# 9_LPDDR4_SDRAM1.net
KiCad netlist of a schematic drawn in Altium Designer
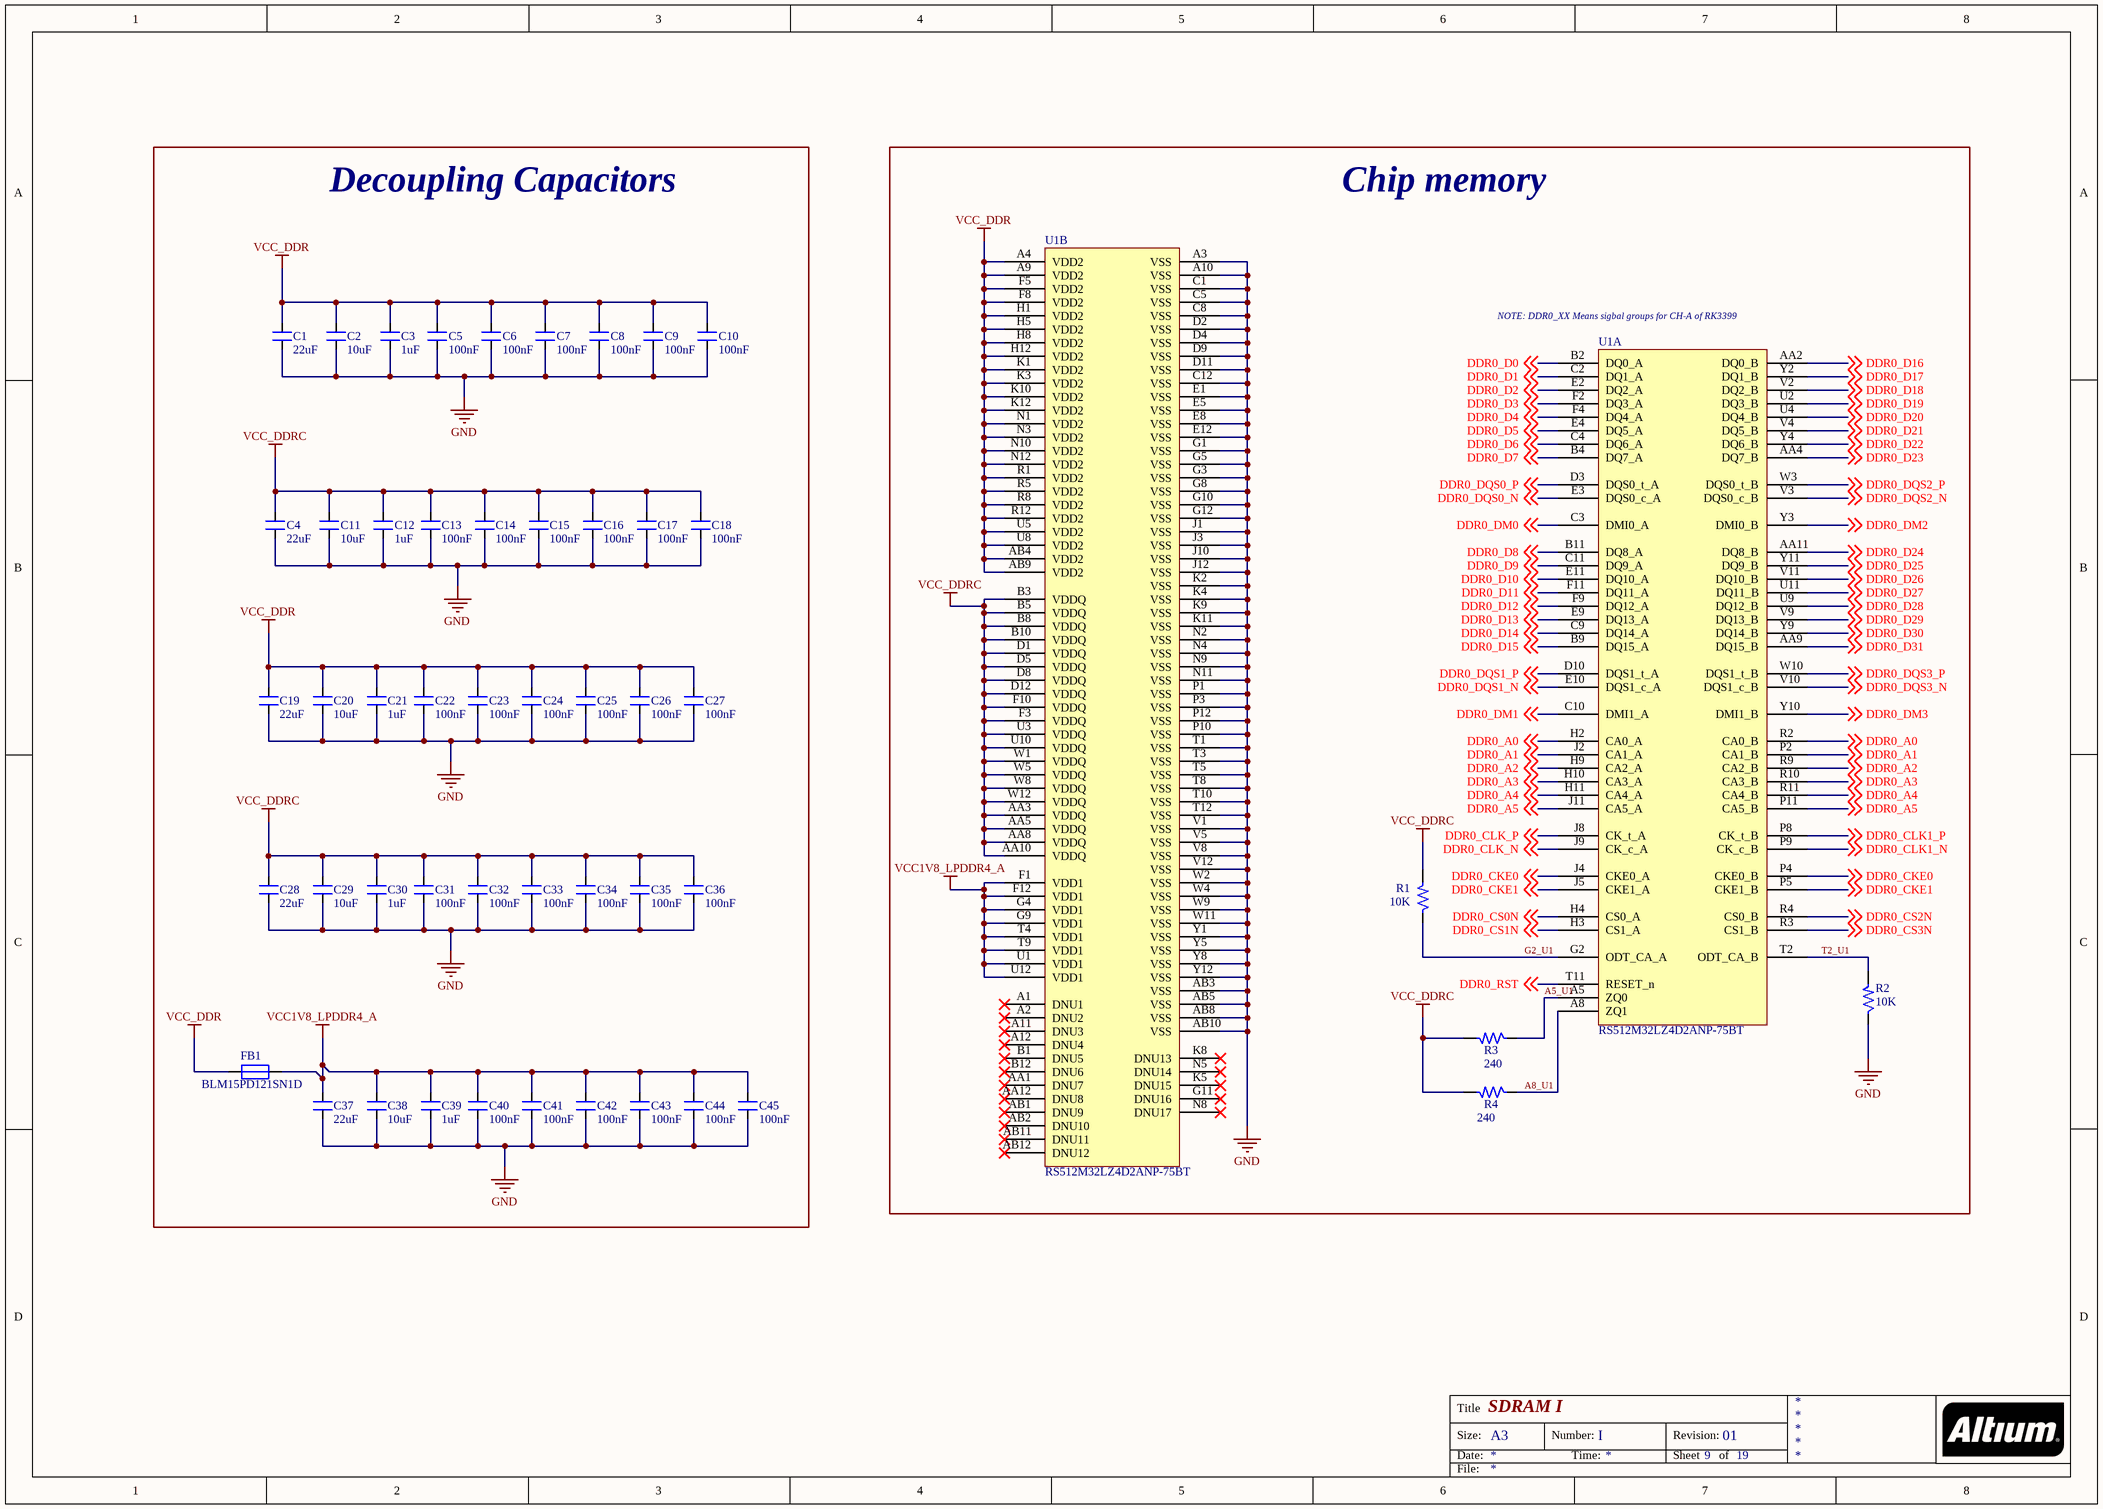
[diagram p0: [9] LPDDR4_SDRAM1.SchDoc]

(export (version "E")
  (design (tool "Eeschema 10.0.6"))
  (components
    (comp (ref "C1")
      (value "22uF")
      (footprint "CAP_0402")
      (description "22µF ±20% 6.3V Ceramic Capacitor X5R 0402 (1005 Metric)")
      (fields
        (field (name "MANUFACTURER") "Murata Electronics")
        (field (name "MANUFACTURER PART NUMBER") "CL05A226MQ5N6J8")
      )
      (libsource (lib "EsteemPCB_SOM_Course_intlib") (part "CAP_22uF-6.3V-20%-0402"))
    )
    (comp (ref "C2")
      (value "10uF")
      (footprint "CAP_0402")
      (description "10µF ±20% 10V Ceramic Capacitor X5R 0402 (1005 Metric)")
      (fields
        (field (name "MANUFACTURER PART NUMBER") "CL05A106MP5NUNC")
        (field (name "MANUFACTURER") "Samsung Electro-Mechanics")
      )
      (libsource (lib "EsteemPCB_SOM_Course_intlib") (part "CAP_10uF-10V-20%-0402"))
    )
    (comp (ref "C3")
      (value "1uF")
      (footprint "CAP_0201")
      (description "1µF ±20% 16V Ceramic Capacitor X5R 0201 (0603 Metric)")
      (fields
        (field (name "MANUFACTURER") "Samsung Electro-Mechanics")
        (field (name "MANUFACTURER PART NUMBER") "CL03A105MO3NRNH")
      )
      (libsource (lib "EsteemPCB_SOM_Course_intlib") (part "CAP_1uF-16V-10%-0201"))
    )
    (comp (ref "C4")
      (value "22uF")
      (footprint "CAP_0402")
      (description "22µF ±20% 6.3V Ceramic Capacitor X5R 0402 (1005 Metric)")
      (fields
        (field (name "MANUFACTURER") "Murata Electronics")
        (field (name "MANUFACTURER PART NUMBER") "CL05A226MQ5N6J8")
      )
      (libsource (lib "EsteemPCB_SOM_Course_intlib") (part "CAP_22uF-6.3V-20%-0402"))
    )
    (comp (ref "C5")
      (value "100nF")
      (footprint "CAP_0201")
      (description "0.1µF ±10% 25V Ceramic Capacitor X5R 0201 (0603 Metric)")
      (fields
        (field (name "MANUFACTURER") "TDK Corporation")
        (field (name "MANUFACTURER PART NUMBER") "C0603X5R1E104K030BB")
      )
      (libsource (lib "EsteemPCB_SOM_Course_intlib") (part "CAP_100nF-25V-10%-0201"))
    )
    (comp (ref "C6")
      (value "100nF")
      (footprint "CAP_0201")
      (description "0.1µF ±10% 25V Ceramic Capacitor X5R 0201 (0603 Metric)")
      (fields
        (field (name "MANUFACTURER") "TDK Corporation")
        (field (name "MANUFACTURER PART NUMBER") "C0603X5R1E104K030BB")
      )
      (libsource (lib "EsteemPCB_SOM_Course_intlib") (part "CAP_100nF-25V-10%-0201"))
    )
    (comp (ref "C7")
      (value "100nF")
      (footprint "CAP_0201")
      (description "0.1µF ±10% 25V Ceramic Capacitor X5R 0201 (0603 Metric)")
      (fields
        (field (name "MANUFACTURER") "TDK Corporation")
        (field (name "MANUFACTURER PART NUMBER") "C0603X5R1E104K030BB")
      )
      (libsource (lib "EsteemPCB_SOM_Course_intlib") (part "CAP_100nF-25V-10%-0201"))
    )
    (comp (ref "C8")
      (value "100nF")
      (footprint "CAP_0201")
      (description "0.1µF ±10% 25V Ceramic Capacitor X5R 0201 (0603 Metric)")
      (fields
        (field (name "MANUFACTURER") "TDK Corporation")
        (field (name "MANUFACTURER PART NUMBER") "C0603X5R1E104K030BB")
      )
      (libsource (lib "EsteemPCB_SOM_Course_intlib") (part "CAP_100nF-25V-10%-0201"))
    )
    (comp (ref "C9")
      (value "100nF")
      (footprint "CAP_0201")
      (description "0.1µF ±10% 25V Ceramic Capacitor X5R 0201 (0603 Metric)")
      (fields
        (field (name "MANUFACTURER") "TDK Corporation")
        (field (name "MANUFACTURER PART NUMBER") "C0603X5R1E104K030BB")
      )
      (libsource (lib "EsteemPCB_SOM_Course_intlib") (part "CAP_100nF-25V-10%-0201"))
    )
    (comp (ref "C10")
      (value "100nF")
      (footprint "CAP_0201")
      (description "0.1µF ±10% 25V Ceramic Capacitor X5R 0201 (0603 Metric)")
      (fields
        (field (name "MANUFACTURER") "TDK Corporation")
        (field (name "MANUFACTURER PART NUMBER") "C0603X5R1E104K030BB")
      )
      (libsource (lib "EsteemPCB_SOM_Course_intlib") (part "CAP_100nF-25V-10%-0201"))
    )
    (comp (ref "C11")
      (value "10uF")
      (footprint "CAP_0402")
      (description "10µF ±20% 10V Ceramic Capacitor X5R 0402 (1005 Metric)")
      (fields
        (field (name "MANUFACTURER PART NUMBER") "CL05A106MP5NUNC")
        (field (name "MANUFACTURER") "Samsung Electro-Mechanics")
      )
      (libsource (lib "EsteemPCB_SOM_Course_intlib") (part "CAP_10uF-10V-20%-0402"))
    )
    (comp (ref "C12")
      (value "1uF")
      (footprint "CAP_0201")
      (description "1µF ±20% 16V Ceramic Capacitor X5R 0201 (0603 Metric)")
      (fields
        (field (name "MANUFACTURER") "Samsung Electro-Mechanics")
        (field (name "MANUFACTURER PART NUMBER") "CL03A105MO3NRNH")
      )
      (libsource (lib "EsteemPCB_SOM_Course_intlib") (part "CAP_1uF-16V-10%-0201"))
    )
    (comp (ref "C13")
      (value "100nF")
      (footprint "CAP_0201")
      (description "0.1µF ±10% 25V Ceramic Capacitor X5R 0201 (0603 Metric)")
      (fields
        (field (name "MANUFACTURER") "TDK Corporation")
        (field (name "MANUFACTURER PART NUMBER") "C0603X5R1E104K030BB")
      )
      (libsource (lib "EsteemPCB_SOM_Course_intlib") (part "CAP_100nF-25V-10%-0201"))
    )
    (comp (ref "C14")
      (value "100nF")
      (footprint "CAP_0201")
      (description "0.1µF ±10% 25V Ceramic Capacitor X5R 0201 (0603 Metric)")
      (fields
        (field (name "MANUFACTURER") "TDK Corporation")
        (field (name "MANUFACTURER PART NUMBER") "C0603X5R1E104K030BB")
      )
      (libsource (lib "EsteemPCB_SOM_Course_intlib") (part "CAP_100nF-25V-10%-0201"))
    )
    (comp (ref "C15")
      (value "100nF")
      (footprint "CAP_0201")
      (description "0.1µF ±10% 25V Ceramic Capacitor X5R 0201 (0603 Metric)")
      (fields
        (field (name "MANUFACTURER") "TDK Corporation")
        (field (name "MANUFACTURER PART NUMBER") "C0603X5R1E104K030BB")
      )
      (libsource (lib "EsteemPCB_SOM_Course_intlib") (part "CAP_100nF-25V-10%-0201"))
    )
    (comp (ref "C16")
      (value "100nF")
      (footprint "CAP_0201")
      (description "0.1µF ±10% 25V Ceramic Capacitor X5R 0201 (0603 Metric)")
      (fields
        (field (name "MANUFACTURER") "TDK Corporation")
        (field (name "MANUFACTURER PART NUMBER") "C0603X5R1E104K030BB")
      )
      (libsource (lib "EsteemPCB_SOM_Course_intlib") (part "CAP_100nF-25V-10%-0201"))
    )
    (comp (ref "C17")
      (value "100nF")
      (footprint "CAP_0201")
      (description "0.1µF ±10% 25V Ceramic Capacitor X5R 0201 (0603 Metric)")
      (fields
        (field (name "MANUFACTURER") "TDK Corporation")
        (field (name "MANUFACTURER PART NUMBER") "C0603X5R1E104K030BB")
      )
      (libsource (lib "EsteemPCB_SOM_Course_intlib") (part "CAP_100nF-25V-10%-0201"))
    )
    (comp (ref "C18")
      (value "100nF")
      (footprint "CAP_0201")
      (description "0.1µF ±10% 25V Ceramic Capacitor X5R 0201 (0603 Metric)")
      (fields
        (field (name "MANUFACTURER") "TDK Corporation")
        (field (name "MANUFACTURER PART NUMBER") "C0603X5R1E104K030BB")
      )
      (libsource (lib "EsteemPCB_SOM_Course_intlib") (part "CAP_100nF-25V-10%-0201"))
    )
    (comp (ref "C19")
      (value "22uF")
      (footprint "CAP_0402")
      (description "22µF ±20% 6.3V Ceramic Capacitor X5R 0402 (1005 Metric)")
      (fields
        (field (name "MANUFACTURER") "Murata Electronics")
        (field (name "MANUFACTURER PART NUMBER") "CL05A226MQ5N6J8")
      )
      (libsource (lib "EsteemPCB_SOM_Course_intlib") (part "CAP_22uF-6.3V-20%-0402"))
    )
    (comp (ref "C20")
      (value "10uF")
      (footprint "CAP_0402")
      (description "10µF ±20% 10V Ceramic Capacitor X5R 0402 (1005 Metric)")
      (fields
        (field (name "MANUFACTURER PART NUMBER") "CL05A106MP5NUNC")
        (field (name "MANUFACTURER") "Samsung Electro-Mechanics")
      )
      (libsource (lib "EsteemPCB_SOM_Course_intlib") (part "CAP_10uF-10V-20%-0402"))
    )
    (comp (ref "C21")
      (value "1uF")
      (footprint "CAP_0201")
      (description "1µF ±20% 16V Ceramic Capacitor X5R 0201 (0603 Metric)")
      (fields
        (field (name "MANUFACTURER") "Samsung Electro-Mechanics")
        (field (name "MANUFACTURER PART NUMBER") "CL03A105MO3NRNH")
      )
      (libsource (lib "EsteemPCB_SOM_Course_intlib") (part "CAP_1uF-16V-10%-0201"))
    )
    (comp (ref "C22")
      (value "100nF")
      (footprint "CAP_0201")
      (description "0.1µF ±10% 25V Ceramic Capacitor X5R 0201 (0603 Metric)")
      (fields
        (field (name "MANUFACTURER") "TDK Corporation")
        (field (name "MANUFACTURER PART NUMBER") "C0603X5R1E104K030BB")
      )
      (libsource (lib "EsteemPCB_SOM_Course_intlib") (part "CAP_100nF-25V-10%-0201"))
    )
    (comp (ref "C23")
      (value "100nF")
      (footprint "CAP_0201")
      (description "0.1µF ±10% 25V Ceramic Capacitor X5R 0201 (0603 Metric)")
      (fields
        (field (name "MANUFACTURER") "TDK Corporation")
        (field (name "MANUFACTURER PART NUMBER") "C0603X5R1E104K030BB")
      )
      (libsource (lib "EsteemPCB_SOM_Course_intlib") (part "CAP_100nF-25V-10%-0201"))
    )
    (comp (ref "C24")
      (value "100nF")
      (footprint "CAP_0201")
      (description "0.1µF ±10% 25V Ceramic Capacitor X5R 0201 (0603 Metric)")
      (fields
        (field (name "MANUFACTURER") "TDK Corporation")
        (field (name "MANUFACTURER PART NUMBER") "C0603X5R1E104K030BB")
      )
      (libsource (lib "EsteemPCB_SOM_Course_intlib") (part "CAP_100nF-25V-10%-0201"))
    )
    (comp (ref "C25")
      (value "100nF")
      (footprint "CAP_0201")
      (description "0.1µF ±10% 25V Ceramic Capacitor X5R 0201 (0603 Metric)")
      (fields
        (field (name "MANUFACTURER") "TDK Corporation")
        (field (name "MANUFACTURER PART NUMBER") "C0603X5R1E104K030BB")
      )
      (libsource (lib "EsteemPCB_SOM_Course_intlib") (part "CAP_100nF-25V-10%-0201"))
    )
    (comp (ref "C26")
      (value "100nF")
      (footprint "CAP_0201")
      (description "0.1µF ±10% 25V Ceramic Capacitor X5R 0201 (0603 Metric)")
      (fields
        (field (name "MANUFACTURER") "TDK Corporation")
        (field (name "MANUFACTURER PART NUMBER") "C0603X5R1E104K030BB")
      )
      (libsource (lib "EsteemPCB_SOM_Course_intlib") (part "CAP_100nF-25V-10%-0201"))
    )
    (comp (ref "C27")
      (value "100nF")
      (footprint "CAP_0201")
      (description "0.1µF ±10% 25V Ceramic Capacitor X5R 0201 (0603 Metric)")
      (fields
        (field (name "MANUFACTURER") "TDK Corporation")
        (field (name "MANUFACTURER PART NUMBER") "C0603X5R1E104K030BB")
      )
      (libsource (lib "EsteemPCB_SOM_Course_intlib") (part "CAP_100nF-25V-10%-0201"))
    )
    (comp (ref "C28")
      (value "22uF")
      (footprint "CAP_0402")
      (description "22µF ±20% 6.3V Ceramic Capacitor X5R 0402 (1005 Metric)")
      (fields
        (field (name "MANUFACTURER") "Murata Electronics")
        (field (name "MANUFACTURER PART NUMBER") "CL05A226MQ5N6J8")
      )
      (libsource (lib "EsteemPCB_SOM_Course_intlib") (part "CAP_22uF-6.3V-20%-0402"))
    )
    (comp (ref "C29")
      (value "10uF")
      (footprint "CAP_0402")
      (description "10µF ±20% 10V Ceramic Capacitor X5R 0402 (1005 Metric)")
      (fields
        (field (name "MANUFACTURER PART NUMBER") "CL05A106MP5NUNC")
        (field (name "MANUFACTURER") "Samsung Electro-Mechanics")
      )
      (libsource (lib "EsteemPCB_SOM_Course_intlib") (part "CAP_10uF-10V-20%-0402"))
    )
    (comp (ref "C30")
      (value "1uF")
      (footprint "CAP_0201")
      (description "1µF ±20% 16V Ceramic Capacitor X5R 0201 (0603 Metric)")
      (fields
        (field (name "MANUFACTURER") "Samsung Electro-Mechanics")
        (field (name "MANUFACTURER PART NUMBER") "CL03A105MO3NRNH")
      )
      (libsource (lib "EsteemPCB_SOM_Course_intlib") (part "CAP_1uF-16V-10%-0201"))
    )
    (comp (ref "C31")
      (value "100nF")
      (footprint "CAP_0201")
      (description "0.1µF ±10% 25V Ceramic Capacitor X5R 0201 (0603 Metric)")
      (fields
        (field (name "MANUFACTURER") "TDK Corporation")
        (field (name "MANUFACTURER PART NUMBER") "C0603X5R1E104K030BB")
      )
      (libsource (lib "EsteemPCB_SOM_Course_intlib") (part "CAP_100nF-25V-10%-0201"))
    )
    (comp (ref "C32")
      (value "100nF")
      (footprint "CAP_0201")
      (description "0.1µF ±10% 25V Ceramic Capacitor X5R 0201 (0603 Metric)")
      (fields
        (field (name "MANUFACTURER") "TDK Corporation")
        (field (name "MANUFACTURER PART NUMBER") "C0603X5R1E104K030BB")
      )
      (libsource (lib "EsteemPCB_SOM_Course_intlib") (part "CAP_100nF-25V-10%-0201"))
    )
    (comp (ref "C33")
      (value "100nF")
      (footprint "CAP_0201")
      (description "0.1µF ±10% 25V Ceramic Capacitor X5R 0201 (0603 Metric)")
      (fields
        (field (name "MANUFACTURER") "TDK Corporation")
        (field (name "MANUFACTURER PART NUMBER") "C0603X5R1E104K030BB")
      )
      (libsource (lib "EsteemPCB_SOM_Course_intlib") (part "CAP_100nF-25V-10%-0201"))
    )
    (comp (ref "C34")
      (value "100nF")
      (footprint "CAP_0201")
      (description "0.1µF ±10% 25V Ceramic Capacitor X5R 0201 (0603 Metric)")
      (fields
        (field (name "MANUFACTURER") "TDK Corporation")
        (field (name "MANUFACTURER PART NUMBER") "C0603X5R1E104K030BB")
      )
      (libsource (lib "EsteemPCB_SOM_Course_intlib") (part "CAP_100nF-25V-10%-0201"))
    )
    (comp (ref "C35")
      (value "100nF")
      (footprint "CAP_0201")
      (description "0.1µF ±10% 25V Ceramic Capacitor X5R 0201 (0603 Metric)")
      (fields
        (field (name "MANUFACTURER") "TDK Corporation")
        (field (name "MANUFACTURER PART NUMBER") "C0603X5R1E104K030BB")
      )
      (libsource (lib "EsteemPCB_SOM_Course_intlib") (part "CAP_100nF-25V-10%-0201"))
    )
    (comp (ref "C36")
      (value "100nF")
      (footprint "CAP_0201")
      (description "0.1µF ±10% 25V Ceramic Capacitor X5R 0201 (0603 Metric)")
      (fields
        (field (name "MANUFACTURER") "TDK Corporation")
        (field (name "MANUFACTURER PART NUMBER") "C0603X5R1E104K030BB")
      )
      (libsource (lib "EsteemPCB_SOM_Course_intlib") (part "CAP_100nF-25V-10%-0201"))
    )
    (comp (ref "C37")
      (value "22uF")
      (footprint "CAP_0402")
      (description "22µF ±20% 6.3V Ceramic Capacitor X5R 0402 (1005 Metric)")
      (fields
        (field (name "MANUFACTURER") "Murata Electronics")
        (field (name "MANUFACTURER PART NUMBER") "CL05A226MQ5N6J8")
      )
      (libsource (lib "EsteemPCB_SOM_Course_intlib") (part "CAP_22uF-6.3V-20%-0402"))
    )
    (comp (ref "C38")
      (value "10uF")
      (footprint "CAP_0402")
      (description "10µF ±20% 10V Ceramic Capacitor X5R 0402 (1005 Metric)")
      (fields
        (field (name "MANUFACTURER PART NUMBER") "CL05A106MP5NUNC")
        (field (name "MANUFACTURER") "Samsung Electro-Mechanics")
      )
      (libsource (lib "EsteemPCB_SOM_Course_intlib") (part "CAP_10uF-10V-20%-0402"))
    )
    (comp (ref "C39")
      (value "1uF")
      (footprint "CAP_0201")
      (description "1µF ±20% 16V Ceramic Capacitor X5R 0201 (0603 Metric)")
      (fields
        (field (name "MANUFACTURER") "Samsung Electro-Mechanics")
        (field (name "MANUFACTURER PART NUMBER") "CL03A105MO3NRNH")
      )
      (libsource (lib "EsteemPCB_SOM_Course_intlib") (part "CAP_1uF-16V-10%-0201"))
    )
    (comp (ref "C40")
      (value "100nF")
      (footprint "CAP_0201")
      (description "0.1µF ±10% 25V Ceramic Capacitor X5R 0201 (0603 Metric)")
      (fields
        (field (name "MANUFACTURER") "TDK Corporation")
        (field (name "MANUFACTURER PART NUMBER") "C0603X5R1E104K030BB")
      )
      (libsource (lib "EsteemPCB_SOM_Course_intlib") (part "CAP_100nF-25V-10%-0201"))
    )
    (comp (ref "C41")
      (value "100nF")
      (footprint "CAP_0201")
      (description "0.1µF ±10% 25V Ceramic Capacitor X5R 0201 (0603 Metric)")
      (fields
        (field (name "MANUFACTURER") "TDK Corporation")
        (field (name "MANUFACTURER PART NUMBER") "C0603X5R1E104K030BB")
      )
      (libsource (lib "EsteemPCB_SOM_Course_intlib") (part "CAP_100nF-25V-10%-0201"))
    )
    (comp (ref "C42")
      (value "100nF")
      (footprint "CAP_0201")
      (description "0.1µF ±10% 25V Ceramic Capacitor X5R 0201 (0603 Metric)")
      (fields
        (field (name "MANUFACTURER") "TDK Corporation")
        (field (name "MANUFACTURER PART NUMBER") "C0603X5R1E104K030BB")
      )
      (libsource (lib "EsteemPCB_SOM_Course_intlib") (part "CAP_100nF-25V-10%-0201"))
    )
    (comp (ref "C43")
      (value "100nF")
      (footprint "CAP_0201")
      (description "0.1µF ±10% 25V Ceramic Capacitor X5R 0201 (0603 Metric)")
      (fields
        (field (name "MANUFACTURER") "TDK Corporation")
        (field (name "MANUFACTURER PART NUMBER") "C0603X5R1E104K030BB")
      )
      (libsource (lib "EsteemPCB_SOM_Course_intlib") (part "CAP_100nF-25V-10%-0201"))
    )
    (comp (ref "C44")
      (value "100nF")
      (footprint "CAP_0201")
      (description "0.1µF ±10% 25V Ceramic Capacitor X5R 0201 (0603 Metric)")
      (fields
        (field (name "MANUFACTURER") "TDK Corporation")
        (field (name "MANUFACTURER PART NUMBER") "C0603X5R1E104K030BB")
      )
      (libsource (lib "EsteemPCB_SOM_Course_intlib") (part "CAP_100nF-25V-10%-0201"))
    )
    (comp (ref "C45")
      (value "100nF")
      (footprint "CAP_0201")
      (description "0.1µF ±10% 25V Ceramic Capacitor X5R 0201 (0603 Metric)")
      (fields
        (field (name "MANUFACTURER") "TDK Corporation")
        (field (name "MANUFACTURER PART NUMBER") "C0603X5R1E104K030BB")
      )
      (libsource (lib "EsteemPCB_SOM_Course_intlib") (part "CAP_100nF-25V-10%-0201"))
    )
    (comp (ref "FB1")
      (value "BLM15PD121SN1D")
      (footprint "RES_0402")
      (description "120 Ohms @ 100MHz 1 Power Line Ferrite Bead 0402 (1005 Metric) 1.3A 90mOhm")
      (fields (field (name "MANUFACTURER") "Murata Electronics"))
      (libsource (lib "EsteemPCB_SOM_Course_intlib") (part "FB_120R-1.3A-100Mhz-0402"))
    )
    (comp (ref "R1")
      (value "10K")
      (footprint "RES_0201")
      (description "10 kOhms ±1% 0.05W, 1/20W Chip Resistor 0201 (0603 Metric) Thick Film")
      (fields
        (field (name "MANUFACTURER") "Stackpole Electronics Inc")
        (field (name "MANUFACTURER PART NUMBER") "RMCF0201FT10K0")
      )
      (libsource (lib "EsteemPCB_SOM_Course_intlib") (part "RES_10K-0.05W-1%-0201"))
    )
    (comp (ref "R2")
      (value "10K")
      (footprint "RES_0201")
      (description "10 kOhms ±1% 0.05W, 1/20W Chip Resistor 0201 (0603 Metric) Thick Film")
      (fields
        (field (name "MANUFACTURER") "Stackpole Electronics Inc")
        (field (name "MANUFACTURER PART NUMBER") "RMCF0201FT10K0")
      )
      (libsource (lib "EsteemPCB_SOM_Course_intlib") (part "RES_10K-0.05W-1%-0201"))
    )
    (comp (ref "R3")
      (value "240")
      (footprint "RES_0201")
      (description "10 kOhms ±1% 0.05W, 1/20W Chip Resistor 0201 (0603 Metric) Thick Film")
      (fields
        (field (name "MANUFACTURER") "Stackpole Electronics Inc")
        (field (name "MANUFACTURER PART NUMBER") "RMCF0201FT10K0")
      )
      (libsource (lib "EsteemPCB_SOM_Course_intlib") (part "RES_10K-0.05W-1%-0201"))
    )
    (comp (ref "R4")
      (value "240")
      (footprint "RES_0201")
      (description "10 kOhms ±1% 0.05W, 1/20W Chip Resistor 0201 (0603 Metric) Thick Film")
      (fields
        (field (name "MANUFACTURER") "Stackpole Electronics Inc")
        (field (name "MANUFACTURER PART NUMBER") "RMCF0201FT10K0")
      )
      (libsource (lib "EsteemPCB_SOM_Course_intlib") (part "RES_10K-0.05W-1%-0201"))
    )
    (comp (ref "U1")
      (value "RS512M32LZ4D2ANP-75BT")
      (footprint "FBGA200_SMD")
      (fields (field (name "MANUFACTURER") "RAYSON"))
      (libsource (lib "EsteemPCB_SOM_Course_intlib") (part "IC_RS512M32LZ4D2ANP-75BT"))
    )
  )
  (nets
    (net (code "1") (name "/A5_U1") (class "Default")
      (node (ref "R3") (pin "1") (pinfunction "1_1") (pintype "passive"))
      (node (ref "U1") (pin "A5") (pinfunction "ZQ0_A5") (pintype "passive"))
    )
    (net (code "2") (name "/A8_U1") (class "Default")
      (node (ref "R4") (pin "1") (pinfunction "1_1") (pintype "passive"))
      (node (ref "U1") (pin "A8") (pinfunction "ZQ1_A8") (pintype "passive"))
    )
    (net (code "3") (name "/G2_U1") (class "Default")
      (node (ref "R1") (pin "1") (pinfunction "1_1") (pintype "passive"))
      (node (ref "U1") (pin "G2") (pinfunction "ODT_CA_A_G2") (pintype "passive"))
    )
    (net (code "4") (name "/T2_U1") (class "Default")
      (node (ref "R2") (pin "2") (pinfunction "2_2") (pintype "passive"))
      (node (ref "U1") (pin "T2") (pinfunction "ODT_CA_B_T2") (pintype "passive"))
    )
    (net (code "5") (name "DDR0_A0") (class "Default")
      (node (ref "U1") (pin "H2") (pinfunction "CA0_A_H2") (pintype "passive"))
      (node (ref "U1") (pin "R2") (pinfunction "CA0_B_R2") (pintype "passive"))
    )
    (net (code "6") (name "DDR0_A1") (class "Default")
      (node (ref "U1") (pin "J2") (pinfunction "CA1_A_J2") (pintype "passive"))
      (node (ref "U1") (pin "P2") (pinfunction "CA1_B_P2") (pintype "passive"))
    )
    (net (code "7") (name "DDR0_A2") (class "Default")
      (node (ref "U1") (pin "H9") (pinfunction "CA2_A_H9") (pintype "passive"))
      (node (ref "U1") (pin "R9") (pinfunction "CA2_B_R9") (pintype "passive"))
    )
    (net (code "8") (name "DDR0_A3") (class "Default")
      (node (ref "U1") (pin "H10") (pinfunction "CA3_A_H10") (pintype "passive"))
      (node (ref "U1") (pin "R10") (pinfunction "CA3_B_R10") (pintype "passive"))
    )
    (net (code "9") (name "DDR0_A4") (class "Default")
      (node (ref "U1") (pin "H11") (pinfunction "CA4_A_H11") (pintype "passive"))
      (node (ref "U1") (pin "R11") (pinfunction "CA4_B_R11") (pintype "passive"))
    )
    (net (code "10") (name "DDR0_A5") (class "Default")
      (node (ref "U1") (pin "J11") (pinfunction "CA5_A_J11") (pintype "passive"))
      (node (ref "U1") (pin "P11") (pinfunction "CA5_B_P11") (pintype "passive"))
    )
    (net (code "11") (name "DDR0_CKE0") (class "Default")
      (node (ref "U1") (pin "J4") (pinfunction "CKE0_A_J4") (pintype "passive"))
      (node (ref "U1") (pin "P4") (pinfunction "CKE0_B_P4") (pintype "passive"))
    )
    (net (code "12") (name "DDR0_CKE1") (class "Default")
      (node (ref "U1") (pin "J5") (pinfunction "CKE1_A_J5") (pintype "passive"))
      (node (ref "U1") (pin "P5") (pinfunction "CKE1_B_P5") (pintype "passive"))
    )
    (net (code "13") (name "DDR0_CLK1_N") (class "Default")
      (node (ref "U1") (pin "P9") (pinfunction "CK_c_B_P9") (pintype "passive"))
    )
    (net (code "14") (name "DDR0_CLK1_P") (class "Default")
      (node (ref "U1") (pin "P8") (pinfunction "CK_t_B_P8") (pintype "passive"))
    )
    (net (code "15") (name "DDR0_CLK_N") (class "Default")
      (node (ref "U1") (pin "J9") (pinfunction "CK_c_A_J9") (pintype "passive"))
    )
    (net (code "16") (name "DDR0_CLK_P") (class "Default")
      (node (ref "U1") (pin "J8") (pinfunction "CK_t_A_J8") (pintype "passive"))
    )
    (net (code "17") (name "DDR0_CS0N") (class "Default")
      (node (ref "U1") (pin "H4") (pinfunction "CS0_A_H4") (pintype "passive"))
    )
    (net (code "18") (name "DDR0_CS1N") (class "Default")
      (node (ref "U1") (pin "H3") (pinfunction "CS1_A_H3") (pintype "passive"))
    )
    (net (code "19") (name "DDR0_CS2N") (class "Default")
      (node (ref "U1") (pin "R4") (pinfunction "CS0_B_R4") (pintype "passive"))
    )
    (net (code "20") (name "DDR0_CS3N") (class "Default")
      (node (ref "U1") (pin "R3") (pinfunction "CS1_B_R3") (pintype "passive"))
    )
    (net (code "21") (name "DDR0_D0") (class "Default")
      (node (ref "U1") (pin "B2") (pinfunction "DQ0_A_B2") (pintype "passive"))
    )
    (net (code "22") (name "DDR0_D1") (class "Default")
      (node (ref "U1") (pin "C2") (pinfunction "DQ1_A_C2") (pintype "passive"))
    )
    (net (code "23") (name "DDR0_D2") (class "Default")
      (node (ref "U1") (pin "E2") (pinfunction "DQ2_A_E2") (pintype "passive"))
    )
    (net (code "24") (name "DDR0_D3") (class "Default")
      (node (ref "U1") (pin "F2") (pinfunction "DQ3_A_F2") (pintype "passive"))
    )
    (net (code "25") (name "DDR0_D4") (class "Default")
      (node (ref "U1") (pin "F4") (pinfunction "DQ4_A_F4") (pintype "passive"))
    )
    (net (code "26") (name "DDR0_D5") (class "Default")
      (node (ref "U1") (pin "E4") (pinfunction "DQ5_A_E4") (pintype "passive"))
    )
    (net (code "27") (name "DDR0_D6") (class "Default")
      (node (ref "U1") (pin "C4") (pinfunction "DQ6_A_C4") (pintype "passive"))
    )
    (net (code "28") (name "DDR0_D7") (class "Default")
      (node (ref "U1") (pin "B4") (pinfunction "DQ7_A_B4") (pintype "passive"))
    )
    (net (code "29") (name "DDR0_D8") (class "Default")
      (node (ref "U1") (pin "B11") (pinfunction "DQ8_A_B11") (pintype "passive"))
    )
    (net (code "30") (name "DDR0_D9") (class "Default")
      (node (ref "U1") (pin "C11") (pinfunction "DQ9_A_C11") (pintype "passive"))
    )
    (net (code "31") (name "DDR0_D10") (class "Default")
      (node (ref "U1") (pin "E11") (pinfunction "DQ10_A_E11") (pintype "passive"))
    )
    (net (code "32") (name "DDR0_D11") (class "Default")
      (node (ref "U1") (pin "F11") (pinfunction "DQ11_A_F11") (pintype "passive"))
    )
    (net (code "33") (name "DDR0_D12") (class "Default")
      (node (ref "U1") (pin "F9") (pinfunction "DQ12_A_F9") (pintype "passive"))
    )
    (net (code "34") (name "DDR0_D13") (class "Default")
      (node (ref "U1") (pin "E9") (pinfunction "DQ13_A_E9") (pintype "passive"))
    )
    (net (code "35") (name "DDR0_D14") (class "Default")
      (node (ref "U1") (pin "C9") (pinfunction "DQ14_A_C9") (pintype "passive"))
    )
    (net (code "36") (name "DDR0_D15") (class "Default")
      (node (ref "U1") (pin "B9") (pinfunction "DQ15_A_B9") (pintype "passive"))
    )
    (net (code "37") (name "DDR0_D16") (class "Default")
      (node (ref "U1") (pin "AA2") (pinfunction "DQ0_B_AA2") (pintype "passive"))
    )
    (net (code "38") (name "DDR0_D17") (class "Default")
      (node (ref "U1") (pin "Y2") (pinfunction "DQ1_B_Y2") (pintype "passive"))
    )
    (net (code "39") (name "DDR0_D18") (class "Default")
      (node (ref "U1") (pin "V2") (pinfunction "DQ2_B_V2") (pintype "passive"))
    )
    (net (code "40") (name "DDR0_D19") (class "Default")
      (node (ref "U1") (pin "U2") (pinfunction "DQ3_B_U2") (pintype "passive"))
    )
    (net (code "41") (name "DDR0_D20") (class "Default")
      (node (ref "U1") (pin "U4") (pinfunction "DQ4_B_U4") (pintype "passive"))
    )
    (net (code "42") (name "DDR0_D21") (class "Default")
      (node (ref "U1") (pin "V4") (pinfunction "DQ5_B_V4") (pintype "passive"))
    )
    (net (code "43") (name "DDR0_D22") (class "Default")
      (node (ref "U1") (pin "Y4") (pinfunction "DQ6_B_Y4") (pintype "passive"))
    )
    (net (code "44") (name "DDR0_D23") (class "Default")
      (node (ref "U1") (pin "AA4") (pinfunction "DQ7_B_AA4") (pintype "passive"))
    )
    (net (code "45") (name "DDR0_D24") (class "Default")
      (node (ref "U1") (pin "AA11") (pinfunction "DQ8_B_AA11") (pintype "passive"))
    )
    (net (code "46") (name "DDR0_D25") (class "Default")
      (node (ref "U1") (pin "Y11") (pinfunction "DQ9_B_Y11") (pintype "passive"))
    )
    (net (code "47") (name "DDR0_D26") (class "Default")
      (node (ref "U1") (pin "V11") (pinfunction "DQ10_B_V11") (pintype "passive"))
    )
    (net (code "48") (name "DDR0_D27") (class "Default")
      (node (ref "U1") (pin "U11") (pinfunction "DQ11_B_U11") (pintype "passive"))
    )
    (net (code "49") (name "DDR0_D28") (class "Default")
      (node (ref "U1") (pin "U9") (pinfunction "DQ12_B_U9") (pintype "passive"))
    )
    (net (code "50") (name "DDR0_D29") (class "Default")
      (node (ref "U1") (pin "V9") (pinfunction "DQ13_B_V9") (pintype "passive"))
    )
    (net (code "51") (name "DDR0_D30") (class "Default")
      (node (ref "U1") (pin "Y9") (pinfunction "DQ14_B_Y9") (pintype "passive"))
    )
    (net (code "52") (name "DDR0_D31") (class "Default")
      (node (ref "U1") (pin "AA9") (pinfunction "DQ15_B_AA9") (pintype "passive"))
    )
    (net (code "53") (name "DDR0_DM0") (class "Default")
      (node (ref "U1") (pin "C3") (pinfunction "DMI0_A_C3") (pintype "passive"))
    )
    (net (code "54") (name "DDR0_DM1") (class "Default")
      (node (ref "U1") (pin "C10") (pinfunction "DMI1_A_C10") (pintype "passive"))
    )
    (net (code "55") (name "DDR0_DM2") (class "Default")
      (node (ref "U1") (pin "Y3") (pinfunction "DMI0_B_Y3") (pintype "passive"))
    )
    (net (code "56") (name "DDR0_DM3") (class "Default")
      (node (ref "U1") (pin "Y10") (pinfunction "DMI1_B_Y10") (pintype "passive"))
    )
    (net (code "57") (name "DDR0_DQS0_N") (class "Default")
      (node (ref "U1") (pin "E3") (pinfunction "DQS0_c_A_E3") (pintype "passive"))
    )
    (net (code "58") (name "DDR0_DQS0_P") (class "Default")
      (node (ref "U1") (pin "D3") (pinfunction "DQS0_t_A_D3") (pintype "passive"))
    )
    (net (code "59") (name "DDR0_DQS1_N") (class "Default")
      (node (ref "U1") (pin "E10") (pinfunction "DQS1_c_A_E10") (pintype "passive"))
    )
    (net (code "60") (name "DDR0_DQS1_P") (class "Default")
      (node (ref "U1") (pin "D10") (pinfunction "DQS1_t_A_D10") (pintype "passive"))
    )
    (net (code "61") (name "DDR0_DQS2_N") (class "Default")
      (node (ref "U1") (pin "V3") (pinfunction "DQS0_c_B_V3") (pintype "passive"))
    )
    (net (code "62") (name "DDR0_DQS2_P") (class "Default")
      (node (ref "U1") (pin "W3") (pinfunction "DQS0_t_B_W3") (pintype "passive"))
    )
    (net (code "63") (name "DDR0_DQS3_N") (class "Default")
      (node (ref "U1") (pin "V10") (pinfunction "DQS1_c_B_V10") (pintype "passive"))
    )
    (net (code "64") (name "DDR0_DQS3_P") (class "Default")
      (node (ref "U1") (pin "W10") (pinfunction "DQS1_t_B_W10") (pintype "passive"))
    )
    (net (code "65") (name "DDR0_RST") (class "Default")
      (node (ref "U1") (pin "T11") (pinfunction "RESET_n_T11") (pintype "passive"))
    )
    (net (code "66") (name "GND") (class "Default")
      (node (ref "C1") (pin "1") (pinfunction "1_1") (pintype "passive"))
      (node (ref "C10") (pin "1") (pinfunction "1_1") (pintype "passive"))
      (node (ref "C11") (pin "1") (pinfunction "1_1") (pintype "passive"))
      (node (ref "C12") (pin "1") (pinfunction "1_1") (pintype "passive"))
      (node (ref "C13") (pin "1") (pinfunction "1_1") (pintype "passive"))
      (node (ref "C14") (pin "1") (pinfunction "1_1") (pintype "passive"))
      (node (ref "C15") (pin "1") (pinfunction "1_1") (pintype "passive"))
      (node (ref "C16") (pin "1") (pinfunction "1_1") (pintype "passive"))
      (node (ref "C17") (pin "1") (pinfunction "1_1") (pintype "passive"))
      (node (ref "C18") (pin "1") (pinfunction "1_1") (pintype "passive"))
      (node (ref "C19") (pin "1") (pinfunction "1_1") (pintype "passive"))
      (node (ref "C2") (pin "1") (pinfunction "1_1") (pintype "passive"))
      (node (ref "C20") (pin "1") (pinfunction "1_1") (pintype "passive"))
      (node (ref "C21") (pin "1") (pinfunction "1_1") (pintype "passive"))
      (node (ref "C22") (pin "1") (pinfunction "1_1") (pintype "passive"))
      (node (ref "C23") (pin "1") (pinfunction "1_1") (pintype "passive"))
      (node (ref "C24") (pin "1") (pinfunction "1_1") (pintype "passive"))
      (node (ref "C25") (pin "1") (pinfunction "1_1") (pintype "passive"))
      (node (ref "C26") (pin "1") (pinfunction "1_1") (pintype "passive"))
      (node (ref "C27") (pin "1") (pinfunction "1_1") (pintype "passive"))
      (node (ref "C28") (pin "1") (pinfunction "1_1") (pintype "passive"))
      (node (ref "C29") (pin "1") (pinfunction "1_1") (pintype "passive"))
      (node (ref "C3") (pin "1") (pinfunction "1_1") (pintype "passive"))
      (node (ref "C30") (pin "1") (pinfunction "1_1") (pintype "passive"))
      (node (ref "C31") (pin "1") (pinfunction "1_1") (pintype "passive"))
      (node (ref "C32") (pin "1") (pinfunction "1_1") (pintype "passive"))
      (node (ref "C33") (pin "1") (pinfunction "1_1") (pintype "passive"))
      (node (ref "C34") (pin "1") (pinfunction "1_1") (pintype "passive"))
      (node (ref "C35") (pin "1") (pinfunction "1_1") (pintype "passive"))
      (node (ref "C36") (pin "1") (pinfunction "1_1") (pintype "passive"))
      (node (ref "C37") (pin "1") (pinfunction "1_1") (pintype "passive"))
      (node (ref "C38") (pin "1") (pinfunction "1_1") (pintype "passive"))
      (node (ref "C39") (pin "1") (pinfunction "1_1") (pintype "passive"))
      (node (ref "C4") (pin "1") (pinfunction "1_1") (pintype "passive"))
      (node (ref "C40") (pin "1") (pinfunction "1_1") (pintype "passive"))
      (node (ref "C41") (pin "1") (pinfunction "1_1") (pintype "passive"))
      (node (ref "C42") (pin "1") (pinfunction "1_1") (pintype "passive"))
      (node (ref "C43") (pin "1") (pinfunction "1_1") (pintype "passive"))
      (node (ref "C44") (pin "1") (pinfunction "1_1") (pintype "passive"))
      (node (ref "C45") (pin "1") (pinfunction "1_1") (pintype "passive"))
      (node (ref "C5") (pin "1") (pinfunction "1_1") (pintype "passive"))
      (node (ref "C6") (pin "1") (pinfunction "1_1") (pintype "passive"))
      (node (ref "C7") (pin "1") (pinfunction "1_1") (pintype "passive"))
      (node (ref "C8") (pin "1") (pinfunction "1_1") (pintype "passive"))
      (node (ref "C9") (pin "1") (pinfunction "1_1") (pintype "passive"))
      (node (ref "R2") (pin "1") (pinfunction "1_1") (pintype "passive"))
      (node (ref "U1") (pin "A10") (pinfunction "VSS_A10") (pintype "passive"))
      (node (ref "U1") (pin "A3") (pinfunction "VSS_A3") (pintype "passive"))
      (node (ref "U1") (pin "AB10") (pinfunction "VSS_AB10") (pintype "passive"))
      (node (ref "U1") (pin "AB3") (pinfunction "VSS_AB3") (pintype "passive"))
      (node (ref "U1") (pin "AB5") (pinfunction "VSS_AB5") (pintype "passive"))
      (node (ref "U1") (pin "AB8") (pinfunction "VSS_AB8") (pintype "passive"))
      (node (ref "U1") (pin "C1") (pinfunction "VSS_C1") (pintype "passive"))
      (node (ref "U1") (pin "C12") (pinfunction "VSS_C12") (pintype "passive"))
      (node (ref "U1") (pin "C5") (pinfunction "VSS_C5") (pintype "passive"))
      (node (ref "U1") (pin "C8") (pinfunction "VSS_C8") (pintype "passive"))
      (node (ref "U1") (pin "D11") (pinfunction "VSS_D11") (pintype "passive"))
      (node (ref "U1") (pin "D2") (pinfunction "VSS_D2") (pintype "passive"))
      (node (ref "U1") (pin "D4") (pinfunction "VSS_D4") (pintype "passive"))
      (node (ref "U1") (pin "D9") (pinfunction "VSS_D9") (pintype "passive"))
      (node (ref "U1") (pin "E1") (pinfunction "VSS_E1") (pintype "passive"))
      (node (ref "U1") (pin "E12") (pinfunction "VSS_E12") (pintype "passive"))
      (node (ref "U1") (pin "E5") (pinfunction "VSS_E5") (pintype "passive"))
      (node (ref "U1") (pin "E8") (pinfunction "VSS_E8") (pintype "passive"))
      (node (ref "U1") (pin "G1") (pinfunction "VSS_G1") (pintype "passive"))
      (node (ref "U1") (pin "G10") (pinfunction "VSS_G10") (pintype "passive"))
      (node (ref "U1") (pin "G12") (pinfunction "VSS_G12") (pintype "passive"))
      (node (ref "U1") (pin "G3") (pinfunction "VSS_G3") (pintype "passive"))
      (node (ref "U1") (pin "G5") (pinfunction "VSS_G5") (pintype "passive"))
      (node (ref "U1") (pin "G8") (pinfunction "VSS_G8") (pintype "passive"))
      (node (ref "U1") (pin "J1") (pinfunction "VSS_J1") (pintype "passive"))
      (node (ref "U1") (pin "J10") (pinfunction "VSS_J10") (pintype "passive"))
      (node (ref "U1") (pin "J12") (pinfunction "VSS_J12") (pintype "passive"))
      (node (ref "U1") (pin "J3") (pinfunction "VSS_J3") (pintype "passive"))
      (node (ref "U1") (pin "K11") (pinfunction "VSS_K11") (pintype "passive"))
      (node (ref "U1") (pin "K2") (pinfunction "VSS_K2") (pintype "passive"))
      (node (ref "U1") (pin "K4") (pinfunction "VSS_K4") (pintype "passive"))
      (node (ref "U1") (pin "K9") (pinfunction "VSS_K9") (pintype "passive"))
      (node (ref "U1") (pin "N11") (pinfunction "VSS_N11") (pintype "passive"))
      (node (ref "U1") (pin "N2") (pinfunction "VSS_N2") (pintype "passive"))
      (node (ref "U1") (pin "N4") (pinfunction "VSS_N4") (pintype "passive"))
      (node (ref "U1") (pin "N9") (pinfunction "VSS_N9") (pintype "passive"))
      (node (ref "U1") (pin "P1") (pinfunction "VSS_P1") (pintype "passive"))
      (node (ref "U1") (pin "P10") (pinfunction "VSS_P10") (pintype "passive"))
      (node (ref "U1") (pin "P12") (pinfunction "VSS_P12") (pintype "passive"))
      (node (ref "U1") (pin "P3") (pinfunction "VSS_P3") (pintype "passive"))
      (node (ref "U1") (pin "T1") (pinfunction "VSS_T1") (pintype "passive"))
      (node (ref "U1") (pin "T10") (pinfunction "VSS_T10") (pintype "passive"))
      (node (ref "U1") (pin "T12") (pinfunction "VSS_T12") (pintype "passive"))
      (node (ref "U1") (pin "T3") (pinfunction "VSS_T3") (pintype "passive"))
      (node (ref "U1") (pin "T5") (pinfunction "VSS_T5") (pintype "passive"))
      (node (ref "U1") (pin "T8") (pinfunction "VSS_T8") (pintype "passive"))
      (node (ref "U1") (pin "V1") (pinfunction "VSS_V1") (pintype "passive"))
      (node (ref "U1") (pin "V12") (pinfunction "VSS_V12") (pintype "passive"))
      (node (ref "U1") (pin "V5") (pinfunction "VSS_V5") (pintype "passive"))
      (node (ref "U1") (pin "V8") (pinfunction "VSS_V8") (pintype "passive"))
      (node (ref "U1") (pin "W11") (pinfunction "VSS_W11") (pintype "passive"))
      (node (ref "U1") (pin "W2") (pinfunction "VSS_W2") (pintype "passive"))
      (node (ref "U1") (pin "W4") (pinfunction "VSS_W4") (pintype "passive"))
      (node (ref "U1") (pin "W9") (pinfunction "VSS_W9") (pintype "passive"))
      (node (ref "U1") (pin "Y1") (pinfunction "VSS_Y1") (pintype "passive"))
      (node (ref "U1") (pin "Y12") (pinfunction "VSS_Y12") (pintype "passive"))
      (node (ref "U1") (pin "Y5") (pinfunction "VSS_Y5") (pintype "passive"))
      (node (ref "U1") (pin "Y8") (pinfunction "VSS_Y8") (pintype "passive"))
    )
    (net (code "67") (name "VCC1V8_LPDDR4_A") (class "Default")
      (node (ref "C37") (pin "2") (pinfunction "2_2") (pintype "passive"))
      (node (ref "C38") (pin "2") (pinfunction "2_2") (pintype "passive"))
      (node (ref "C39") (pin "2") (pinfunction "2_2") (pintype "passive"))
      (node (ref "C40") (pin "2") (pinfunction "2_2") (pintype "passive"))
      (node (ref "C41") (pin "2") (pinfunction "2_2") (pintype "passive"))
      (node (ref "C42") (pin "2") (pinfunction "2_2") (pintype "passive"))
      (node (ref "C43") (pin "2") (pinfunction "2_2") (pintype "passive"))
      (node (ref "C44") (pin "2") (pinfunction "2_2") (pintype "passive"))
      (node (ref "C45") (pin "2") (pinfunction "2_2") (pintype "passive"))
      (node (ref "FB1") (pin "2") (pinfunction "2_2") (pintype "passive"))
      (node (ref "U1") (pin "F1") (pinfunction "VDD1_F1") (pintype "passive"))
      (node (ref "U1") (pin "F12") (pinfunction "VDD1_F12") (pintype "passive"))
      (node (ref "U1") (pin "G4") (pinfunction "VDD1_G4") (pintype "passive"))
      (node (ref "U1") (pin "G9") (pinfunction "VDD1_G9") (pintype "passive"))
      (node (ref "U1") (pin "T4") (pinfunction "VDD1_T4") (pintype "passive"))
      (node (ref "U1") (pin "T9") (pinfunction "VDD1_T9") (pintype "passive"))
      (node (ref "U1") (pin "U1") (pinfunction "VDD1_U1") (pintype "passive"))
      (node (ref "U1") (pin "U12") (pinfunction "VDD1_U12") (pintype "passive"))
    )
    (net (code "68") (name "VCC_DDR") (class "Default")
      (node (ref "C1") (pin "2") (pinfunction "2_2") (pintype "passive"))
      (node (ref "C10") (pin "2") (pinfunction "2_2") (pintype "passive"))
      (node (ref "C19") (pin "2") (pinfunction "2_2") (pintype "passive"))
      (node (ref "C2") (pin "2") (pinfunction "2_2") (pintype "passive"))
      (node (ref "C20") (pin "2") (pinfunction "2_2") (pintype "passive"))
      (node (ref "C21") (pin "2") (pinfunction "2_2") (pintype "passive"))
      (node (ref "C22") (pin "2") (pinfunction "2_2") (pintype "passive"))
      (node (ref "C23") (pin "2") (pinfunction "2_2") (pintype "passive"))
      (node (ref "C24") (pin "2") (pinfunction "2_2") (pintype "passive"))
      (node (ref "C25") (pin "2") (pinfunction "2_2") (pintype "passive"))
      (node (ref "C26") (pin "2") (pinfunction "2_2") (pintype "passive"))
      (node (ref "C27") (pin "2") (pinfunction "2_2") (pintype "passive"))
      (node (ref "C3") (pin "2") (pinfunction "2_2") (pintype "passive"))
      (node (ref "C5") (pin "2") (pinfunction "2_2") (pintype "passive"))
      (node (ref "C6") (pin "2") (pinfunction "2_2") (pintype "passive"))
      (node (ref "C7") (pin "2") (pinfunction "2_2") (pintype "passive"))
      (node (ref "C8") (pin "2") (pinfunction "2_2") (pintype "passive"))
      (node (ref "C9") (pin "2") (pinfunction "2_2") (pintype "passive"))
      (node (ref "FB1") (pin "1") (pinfunction "1_1") (pintype "passive"))
      (node (ref "U1") (pin "A4") (pinfunction "VDD2_A4") (pintype "passive"))
      (node (ref "U1") (pin "A9") (pinfunction "VDD2_A9") (pintype "passive"))
      (node (ref "U1") (pin "AB4") (pinfunction "VDD2_AB4") (pintype "passive"))
      (node (ref "U1") (pin "AB9") (pinfunction "VDD2_AB9") (pintype "passive"))
      (node (ref "U1") (pin "F5") (pinfunction "VDD2_F5") (pintype "passive"))
      (node (ref "U1") (pin "F8") (pinfunction "VDD2_F8") (pintype "passive"))
      (node (ref "U1") (pin "H1") (pinfunction "VDD2_H1") (pintype "passive"))
      (node (ref "U1") (pin "H12") (pinfunction "VDD2_H12") (pintype "passive"))
      (node (ref "U1") (pin "H5") (pinfunction "VDD2_H5") (pintype "passive"))
      (node (ref "U1") (pin "H8") (pinfunction "VDD2_H8") (pintype "passive"))
      (node (ref "U1") (pin "K1") (pinfunction "VDD2_K1") (pintype "passive"))
      (node (ref "U1") (pin "K10") (pinfunction "VDD2_K10") (pintype "passive"))
      (node (ref "U1") (pin "K12") (pinfunction "VDD2_K12") (pintype "passive"))
      (node (ref "U1") (pin "K3") (pinfunction "VDD2_K3") (pintype "passive"))
      (node (ref "U1") (pin "N1") (pinfunction "VDD2_N1") (pintype "passive"))
      (node (ref "U1") (pin "N10") (pinfunction "VDD2_N10") (pintype "passive"))
      (node (ref "U1") (pin "N12") (pinfunction "VDD2_N12") (pintype "passive"))
      (node (ref "U1") (pin "N3") (pinfunction "VDD2_N3") (pintype "passive"))
      (node (ref "U1") (pin "R1") (pinfunction "VDD2_R1") (pintype "passive"))
      (node (ref "U1") (pin "R12") (pinfunction "VDD2_R12") (pintype "passive"))
      (node (ref "U1") (pin "R5") (pinfunction "VDD2_R5") (pintype "passive"))
      (node (ref "U1") (pin "R8") (pinfunction "VDD2_R8") (pintype "passive"))
      (node (ref "U1") (pin "U5") (pinfunction "VDD2_U5") (pintype "passive"))
      (node (ref "U1") (pin "U8") (pinfunction "VDD2_U8") (pintype "passive"))
    )
    (net (code "69") (name "VCC_DDRC") (class "Default")
      (node (ref "C11") (pin "2") (pinfunction "2_2") (pintype "passive"))
      (node (ref "C12") (pin "2") (pinfunction "2_2") (pintype "passive"))
      (node (ref "C13") (pin "2") (pinfunction "2_2") (pintype "passive"))
      (node (ref "C14") (pin "2") (pinfunction "2_2") (pintype "passive"))
      (node (ref "C15") (pin "2") (pinfunction "2_2") (pintype "passive"))
      (node (ref "C16") (pin "2") (pinfunction "2_2") (pintype "passive"))
      (node (ref "C17") (pin "2") (pinfunction "2_2") (pintype "passive"))
      (node (ref "C18") (pin "2") (pinfunction "2_2") (pintype "passive"))
      (node (ref "C28") (pin "2") (pinfunction "2_2") (pintype "passive"))
      (node (ref "C29") (pin "2") (pinfunction "2_2") (pintype "passive"))
      (node (ref "C30") (pin "2") (pinfunction "2_2") (pintype "passive"))
      (node (ref "C31") (pin "2") (pinfunction "2_2") (pintype "passive"))
      (node (ref "C32") (pin "2") (pinfunction "2_2") (pintype "passive"))
      (node (ref "C33") (pin "2") (pinfunction "2_2") (pintype "passive"))
      (node (ref "C34") (pin "2") (pinfunction "2_2") (pintype "passive"))
      (node (ref "C35") (pin "2") (pinfunction "2_2") (pintype "passive"))
      (node (ref "C36") (pin "2") (pinfunction "2_2") (pintype "passive"))
      (node (ref "C4") (pin "2") (pinfunction "2_2") (pintype "passive"))
      (node (ref "R1") (pin "2") (pinfunction "2_2") (pintype "passive"))
      (node (ref "R3") (pin "2") (pinfunction "2_2") (pintype "passive"))
      (node (ref "R4") (pin "2") (pinfunction "2_2") (pintype "passive"))
      (node (ref "U1") (pin "AA10") (pinfunction "VDDQ_AA10") (pintype "passive"))
      (node (ref "U1") (pin "AA3") (pinfunction "VDDQ_AA3") (pintype "passive"))
      (node (ref "U1") (pin "AA5") (pinfunction "VDDQ_AA5") (pintype "passive"))
      (node (ref "U1") (pin "AA8") (pinfunction "VDDQ_AA8") (pintype "passive"))
      (node (ref "U1") (pin "B10") (pinfunction "VDDQ_B10") (pintype "passive"))
      (node (ref "U1") (pin "B3") (pinfunction "VDDQ_B3") (pintype "passive"))
      (node (ref "U1") (pin "B5") (pinfunction "VDDQ_B5") (pintype "passive"))
      (node (ref "U1") (pin "B8") (pinfunction "VDDQ_B8") (pintype "passive"))
      (node (ref "U1") (pin "D1") (pinfunction "VDDQ_D1") (pintype "passive"))
      (node (ref "U1") (pin "D12") (pinfunction "VDDQ_D12") (pintype "passive"))
      (node (ref "U1") (pin "D5") (pinfunction "VDDQ_D5") (pintype "passive"))
      (node (ref "U1") (pin "D8") (pinfunction "VDDQ_D8") (pintype "passive"))
      (node (ref "U1") (pin "F10") (pinfunction "VDDQ_F10") (pintype "passive"))
      (node (ref "U1") (pin "F3") (pinfunction "VDDQ_F3") (pintype "passive"))
      (node (ref "U1") (pin "U10") (pinfunction "VDDQ_U10") (pintype "passive"))
      (node (ref "U1") (pin "U3") (pinfunction "VDDQ_U3") (pintype "passive"))
      (node (ref "U1") (pin "W1") (pinfunction "VDDQ_W1") (pintype "passive"))
      (node (ref "U1") (pin "W12") (pinfunction "VDDQ_W12") (pintype "passive"))
      (node (ref "U1") (pin "W5") (pinfunction "VDDQ_W5") (pintype "passive"))
      (node (ref "U1") (pin "W8") (pinfunction "VDDQ_W8") (pintype "passive"))
    )
    (net (code "70") (name "unconnected-(U1B-DNU1-PadA1)") (class "Default")
      (node (ref "U1") (pin "A1") (pinfunction "DNU1_A1") (pintype "passive+no_connect"))
    )
    (net (code "71") (name "unconnected-(U1B-DNU2-PadA2)") (class "Default")
      (node (ref "U1") (pin "A2") (pinfunction "DNU2_A2") (pintype "passive+no_connect"))
    )
    (net (code "72") (name "unconnected-(U1B-DNU3-PadA11)") (class "Default")
      (node (ref "U1") (pin "A11") (pinfunction "DNU3_A11") (pintype "passive+no_connect"))
    )
    (net (code "73") (name "unconnected-(U1B-DNU4-PadA12)") (class "Default")
      (node (ref "U1") (pin "A12") (pinfunction "DNU4_A12") (pintype "passive+no_connect"))
    )
    (net (code "74") (name "unconnected-(U1B-DNU5-PadB1)") (class "Default")
      (node (ref "U1") (pin "B1") (pinfunction "DNU5_B1") (pintype "passive+no_connect"))
    )
    (net (code "75") (name "unconnected-(U1B-DNU6-PadB12)") (class "Default")
      (node (ref "U1") (pin "B12") (pinfunction "DNU6_B12") (pintype "passive+no_connect"))
    )
    (net (code "76") (name "unconnected-(U1B-DNU7-PadAA1)") (class "Default")
      (node (ref "U1") (pin "AA1") (pinfunction "DNU7_AA1") (pintype "passive+no_connect"))
    )
    (net (code "77") (name "unconnected-(U1B-DNU8-PadAA12)") (class "Default")
      (node (ref "U1") (pin "AA12") (pinfunction "DNU8_AA12") (pintype "passive+no_connect"))
    )
    (net (code "78") (name "unconnected-(U1B-DNU9-PadAB1)") (class "Default")
      (node (ref "U1") (pin "AB1") (pinfunction "DNU9_AB1") (pintype "passive+no_connect"))
    )
    (net (code "79") (name "unconnected-(U1B-DNU10-PadAB2)") (class "Default")
      (node (ref "U1") (pin "AB2") (pinfunction "DNU10_AB2") (pintype "passive+no_connect"))
    )
    (net (code "80") (name "unconnected-(U1B-DNU11-PadAB11)") (class "Default")
      (node (ref "U1") (pin "AB11") (pinfunction "DNU11_AB11") (pintype "passive+no_connect"))
    )
    (net (code "81") (name "unconnected-(U1B-DNU12-PadAB12)") (class "Default")
      (node (ref "U1") (pin "AB12") (pinfunction "DNU12_AB12") (pintype "passive+no_connect"))
    )
    (net (code "82") (name "unconnected-(U1B-DNU13-PadK8)") (class "Default")
      (node (ref "U1") (pin "K8") (pinfunction "DNU13_K8") (pintype "passive+no_connect"))
    )
    (net (code "83") (name "unconnected-(U1B-DNU14-PadN5)") (class "Default")
      (node (ref "U1") (pin "N5") (pinfunction "DNU14_N5") (pintype "passive+no_connect"))
    )
    (net (code "84") (name "unconnected-(U1B-DNU15-PadK5)") (class "Default")
      (node (ref "U1") (pin "K5") (pinfunction "DNU15_K5") (pintype "passive+no_connect"))
    )
    (net (code "85") (name "unconnected-(U1B-DNU16-PadG11)") (class "Default")
      (node (ref "U1") (pin "G11") (pinfunction "DNU16_G11") (pintype "passive+no_connect"))
    )
    (net (code "86") (name "unconnected-(U1B-DNU17-PadN8)") (class "Default")
      (node (ref "U1") (pin "N8") (pinfunction "DNU17_N8") (pintype "passive+no_connect"))
    )
  )
)
